# ideal-diode.net
KiCad netlist of a schematic drawn in Altium Designer
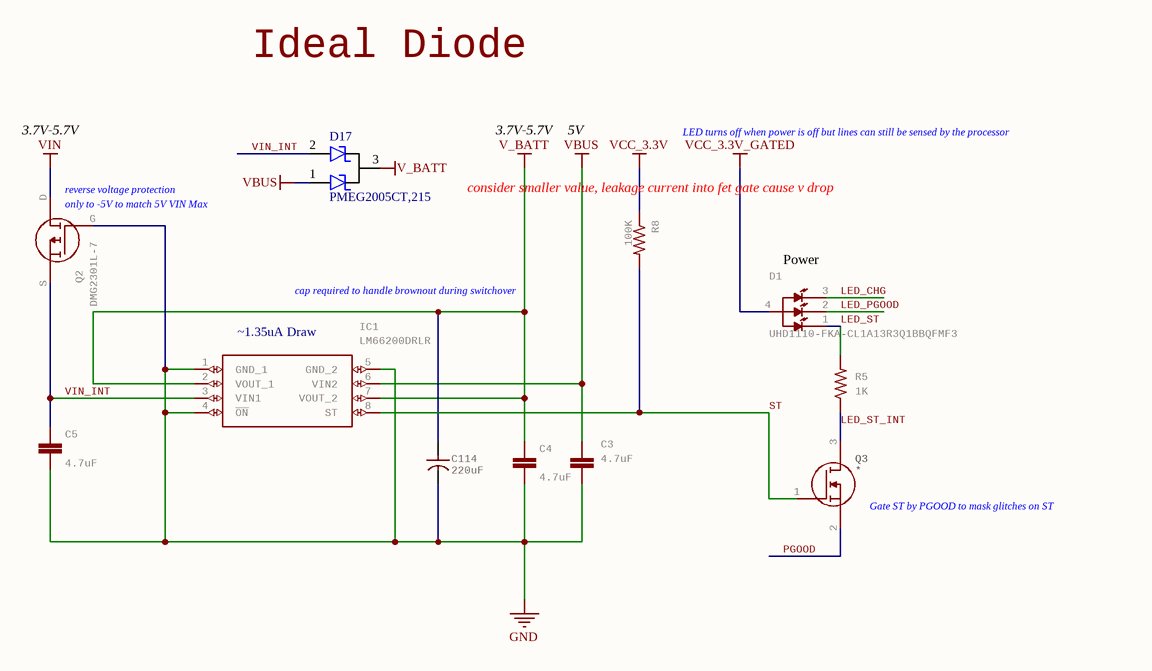
[diagram p0: ideal-diode.SchDoc]

(export (version "E")
  (design (tool "Eeschema 10.0.6"))
  (components
    (comp (ref "C3")
      (value "4.7uF")
      (footprint "0402-CAP")
      (description "CapacitorStandard 0603 ceramic capacitor, and 0.1\" leaded capacitor.")
      (fields (field (name "MPN") "JMK105BBJ475MV-F") (field (name "LIBRARYNAME") "sfe"))
      (libsource (lib "openmv-ae3") (part "CAP0402-CAP"))
    )
    (comp (ref "C4")
      (value "4.7uF")
      (footprint "0402-CAP")
      (description "CapacitorStandard 0603 ceramic capacitor, and 0.1\" leaded capacitor.")
      (fields (field (name "MPN") "JMK105BBJ475MV-F") (field (name "LIBRARYNAME") "sfe"))
      (libsource (lib "openmv-ae3") (part "CAP0402-CAP"))
    )
    (comp (ref "C5")
      (value "4.7uF")
      (footprint "0402-CAP")
      (description "CapacitorStandard 0603 ceramic capacitor, and 0.1\" leaded capacitor.")
      (fields (field (name "MPN") "JMK105BBJ475MV-F") (field (name "LIBRARYNAME") "sfe"))
      (libsource (lib "openmv-ae3") (part "CAP0402-CAP"))
    )
    (comp (ref "C114")
      (value "220uF")
      (footprint "CAP-TANT-1411")
      (fields (field (name "PART NUMBER") "F930J227MBA"))
      (libsource (lib "openmv-ae3") (part "CAP_POL"))
    )
    (comp (ref "D1")
      (value "UHD1110-FKA-CL1A13R3Q1BBQFMF3")
      (footprint "LED_UHD1110-FKA-CL1A13R3Q1BBQFMF3")
      (description "LED RGB SMD, SIZE 1 X 1 mm Check availability")
      (fields (field (name "MF") "Cree Inc.") (field (name "MPN") "UHD1110-FKA-CL1A13r3q1BBQFMF3"))
      (libsource (lib "openmv-ae3") (part "UHD1110-FKA-CL1A13R3Q1BBQFMF3"))
    )
    (comp (ref "D17")
      (value "Dual Schottky")
      (footprint "SOT-23-3")
      (fields
        (field (name "MANUFACTURER") "Nexperia")
        (field (name "PART NUMBER") "PMEG2005CT,215")
        (field (name "MPN") "PMEG2005CT,215")
      )
      (libsource (lib "openmv-ae3") (part "Dual Schottky"))
    )
    (comp (ref "IC1")
      (value "LM66200DRLR")
      (footprint "SOTFL50P160X60-8N")
      (description "1.6-V to 5.5-V, 40-m, 2.5-A, low-IQ, dual ideal diode   Source:  Datasheet")
      (fields (field (name "MOUSER_PART_NUMBER") "595-LM66200DRLR"))
      (libsource (lib "openmv-ae3") (part "LM66200DRLR"))
    )
    (comp (ref "Q2")
      (value "DMG2301L-7")
      (footprint "SOT-23-3-FET")
      (libsource (lib "openmv-ae3") (part "DMG2301L-7"))
    )
    (comp (ref "Q3")
      (value "NMOS")
      (footprint "DFN1006")
      (fields (field (name "MPN") "*"))
      (libsource (lib "openmv-ae3") (part "NMOS"))
    )
    (comp (ref "R5")
      (value "1K")
      (footprint "r0201")
      (description "ResistorBasic schematic elements and footprints for 0603, 1206, and PTH resistors.")
      (fields (field (name "LIBRARYNAME") "sfe"))
      (libsource (lib "openmv-ae3") (part "RESISTOR0402-RES"))
    )
    (comp (ref "R8")
      (value "100K")
      (footprint "r0201")
      (fields (field (name "LIBRARYNAME") "sfe"))
      (libsource (lib "openmv-ae3") (part "RESISTOR0402-RES"))
    )
  )
  (nets
    (net (code "1") (name "/LED_CHG") (class "Default")
      (node (ref "D1") (pin "3") (pinfunction "RED_3") (pintype "passive"))
    )
    (net (code "2") (name "/LED_PGOOD") (class "Default")
      (node (ref "D1") (pin "2") (pinfunction "GREEN_2") (pintype "passive"))
    )
    (net (code "3") (name "/LED_ST") (class "Default")
      (node (ref "D1") (pin "1") (pinfunction "BLUE_1") (pintype "passive"))
      (node (ref "R5") (pin "2") (pinfunction "2_2") (pintype "passive"))
    )
    (net (code "4") (name "/LED_ST_INT") (class "Default")
      (node (ref "Q3") (pin "3") (pinfunction "D_3") (pintype "bidirectional"))
      (node (ref "R5") (pin "1") (pinfunction "1_1") (pintype "passive"))
    )
    (net (code "5") (name "/PGOOD") (class "Default")
      (node (ref "Q3") (pin "2") (pinfunction "S_2") (pintype "bidirectional"))
    )
    (net (code "6") (name "/ST") (class "Default")
      (node (ref "IC1") (pin "8") (pinfunction "ST_8") (pintype "bidirectional"))
      (node (ref "Q3") (pin "1") (pinfunction "G_1") (pintype "bidirectional"))
      (node (ref "R8") (pin "2") (pinfunction "2_2") (pintype "passive"))
    )
    (net (code "7") (name "/VIN_INT") (class "Default")
      (node (ref "C5") (pin "2") (pinfunction "2_2") (pintype "passive"))
      (node (ref "D17") (pin "2") (pinfunction "2_2") (pintype "passive"))
      (node (ref "IC1") (pin "3") (pinfunction "VIN1_3") (pintype "bidirectional"))
      (node (ref "Q2") (pin "S") (pinfunction "S_S") (pintype "bidirectional"))
    )
    (net (code "8") (name "GND") (class "Default")
      (node (ref "C114") (pin "2") (pinfunction "2_2") (pintype "passive"))
      (node (ref "C3") (pin "1") (pinfunction "1_1") (pintype "passive"))
      (node (ref "C4") (pin "1") (pinfunction "1_1") (pintype "passive"))
      (node (ref "C5") (pin "1") (pinfunction "1_1") (pintype "passive"))
      (node (ref "IC1") (pin "1") (pinfunction "GND_1_1") (pintype "bidirectional"))
      (node (ref "IC1") (pin "4") (pinfunction "~{ON}_4") (pintype "bidirectional"))
      (node (ref "IC1") (pin "5") (pinfunction "GND_2_5") (pintype "bidirectional"))
      (node (ref "Q2") (pin "G") (pinfunction "G_G") (pintype "bidirectional"))
    )
    (net (code "9") (name "VBUS") (class "Default")
      (node (ref "C3") (pin "2") (pinfunction "2_2") (pintype "passive"))
      (node (ref "D17") (pin "1") (pinfunction "1_1") (pintype "passive"))
      (node (ref "IC1") (pin "6") (pinfunction "VIN2_6") (pintype "bidirectional"))
    )
    (net (code "10") (name "VCC_3.3V") (class "Default")
      (node (ref "R8") (pin "1") (pinfunction "1_1") (pintype "passive"))
    )
    (net (code "11") (name "VCC_3.3V_GATED") (class "Default")
      (node (ref "D1") (pin "4") (pinfunction "ANODE_4") (pintype "passive"))
    )
    (net (code "12") (name "VIN") (class "Default")
      (node (ref "Q2") (pin "D") (pinfunction "D_D") (pintype "bidirectional"))
    )
    (net (code "13") (name "V_BATT") (class "Default")
      (node (ref "C114") (pin "1") (pinfunction "1_1") (pintype "passive"))
      (node (ref "C4") (pin "2") (pinfunction "2_2") (pintype "passive"))
      (node (ref "D17") (pin "3") (pinfunction "3_3") (pintype "passive"))
      (node (ref "IC1") (pin "2") (pinfunction "VOUT_1_2") (pintype "bidirectional"))
      (node (ref "IC1") (pin "7") (pinfunction "VOUT_2_7") (pintype "bidirectional"))
    )
  )
)
